# Interface.net
KiCad netlist of a schematic drawn in Altium Designer
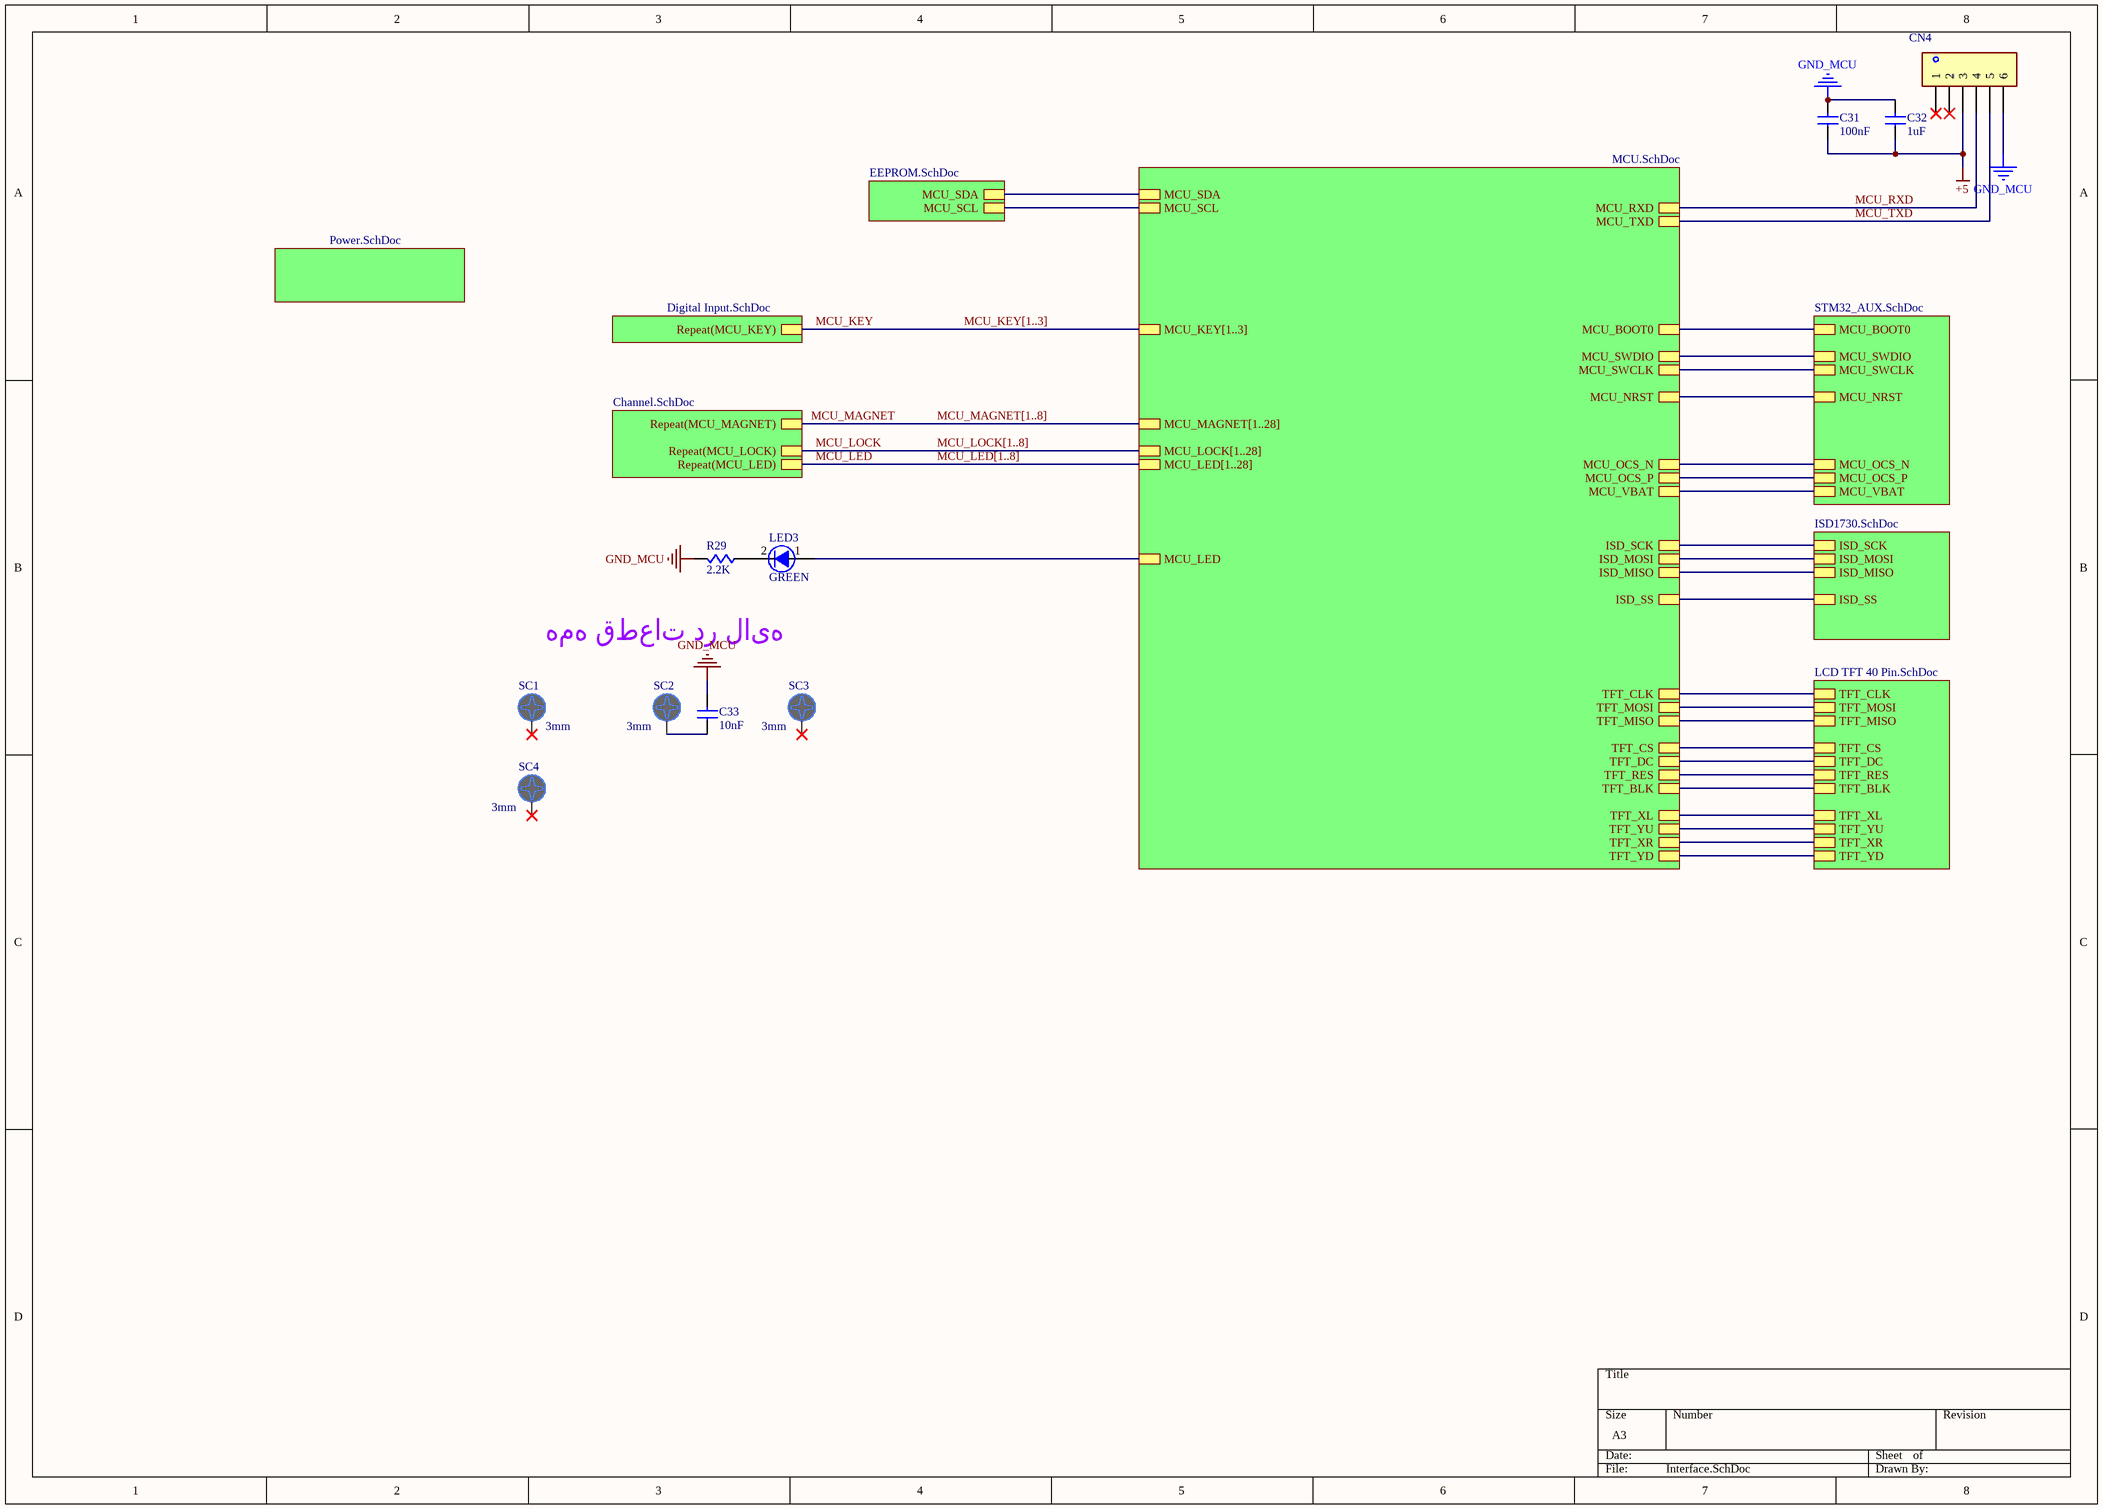
[diagram p0: Interface.SchDoc]

(export (version "E")
  (design (tool "Eeschema 10.0.6"))
  (components
    (comp (ref "C31")
      (value "100nF")
      (footprint "C-0805")
      (description "CAPACITOR")
      (fields
        (field (name "VOLTAGE") "50V")
        (field (name "TOLERANCE") "X7R")
        (field (name "PUBLISHER") "Mahdi Bagherzadeh")
      )
      (libsource (lib "Mahdi-Bagherzadeh") (part "CAP-CER"))
    )
    (comp (ref "C32")
      (value "1uF")
      (footprint "C-0805")
      (description "CAPACITOR")
      (fields
        (field (name "VOLTAGE") "50V")
        (field (name "TOLERANCE") "X7R")
        (field (name "PUBLISHER") "Mahdi Bagherzadeh")
      )
      (libsource (lib "Mahdi-Bagherzadeh") (part "CAP-CER"))
    )
    (comp (ref "C33")
      (value "10nF")
      (footprint "CAP-CER-7x2.5-Ls5")
      (description "CAPACITOR")
      (fields
        (field (name "VOLTAGE") "1KV")
        (field (name "TOLERANCE") "X7R")
        (field (name "PUBLISHER") "Mahdi Bagherzadeh")
      )
      (libsource (lib "Mahdi-Bagherzadeh") (part "CAP-CER"))
    )
    (comp (ref "CN4")
      (value "Connector XH-Straight-THD-2.54mm")
      (footprint "XH-6")
      (description "CONNECTOR")
      (fields (field (name "PUBLISHER") "Mahdi Bagherzadeh"))
      (libsource (lib "Mahdi-Bagherzadeh") (part "CN-6pin"))
    )
    (comp (ref "LED3")
      (value "LED GREEN-1206-SMD")
      (footprint "LED-1206-Y")
      (description "LED")
      (fields (field (name "COLOR") "GREEN") (field (name "PUBLISHER") "Mahdi Bagherzadeh"))
      (libsource (lib "Mahdi-Bagherzadeh") (part "LED"))
    )
    (comp (ref "R29")
      (value "2.2K")
      (footprint "R-0805")
      (description "RESISTOR")
      (fields
        (field (name "TOLERANCE") "5%")
        (field (name "POWER") "1/8W")
        (field (name "PUBLISHER") "Mahdi Bagherzadeh")
      )
      (libsource (lib "Mahdi-Bagherzadeh") (part "RES"))
    )
    (comp (ref "SC1")
      (value "Screw 3mm")
      (footprint "Screw_M3")
      (description "SCREW")
      (fields (field (name "SIZE") "3mm") (field (name "PUBLISHER") "Mahdi Bagherzadeh"))
      (libsource (lib "Mahdi-Bagherzadeh") (part "SCREW"))
    )
    (comp (ref "SC2")
      (value "Screw 3mm")
      (footprint "Screw_M3")
      (description "SCREW")
      (fields (field (name "SIZE") "3mm") (field (name "PUBLISHER") "Mahdi Bagherzadeh"))
      (libsource (lib "Mahdi-Bagherzadeh") (part "SCREW"))
    )
    (comp (ref "SC3")
      (value "Screw 3mm")
      (footprint "Screw_M3")
      (description "SCREW")
      (fields (field (name "SIZE") "3mm") (field (name "PUBLISHER") "Mahdi Bagherzadeh"))
      (libsource (lib "Mahdi-Bagherzadeh") (part "SCREW"))
    )
    (comp (ref "SC4")
      (value "Screw 3mm")
      (footprint "Screw_M3")
      (description "SCREW")
      (fields (field (name "SIZE") "3mm") (field (name "PUBLISHER") "Mahdi Bagherzadeh"))
      (libsource (lib "Mahdi-Bagherzadeh") (part "SCREW"))
    )
  )
  (nets
    (net (code "25") (name "+5") (class "Default")
      (node (ref "C31") (pin "1") (pinfunction "1_1") (pintype "passive"))
      (node (ref "C32") (pin "1") (pinfunction "1_1") (pintype "passive"))
      (node (ref "CN4") (pin "3") (pinfunction "3_3") (pintype "passive"))
    )
    (net (code "34") (name "/MCU_LED_1") (class "Default")
      (node (ref "LED3") (pin "1") (pinfunction "A_1") (pintype "passive"))
    )
    (net (code "42") (name "/MCU_RXD") (class "Default")
      (node (ref "CN4") (pin "4") (pinfunction "4_4") (pintype "passive"))
    )
    (net (code "47") (name "/MCU_TXD") (class "Default")
      (node (ref "CN4") (pin "5") (pinfunction "5_5") (pintype "passive"))
    )
    (net (code "60") (name "GND_MCU") (class "Default")
      (node (ref "C31") (pin "2") (pinfunction "2_2") (pintype "passive"))
      (node (ref "C32") (pin "2") (pinfunction "2_2") (pintype "passive"))
      (node (ref "C33") (pin "2") (pinfunction "2_2") (pintype "passive"))
      (node (ref "CN4") (pin "6") (pinfunction "6_6") (pintype "passive"))
      (node (ref "R29") (pin "2") (pinfunction "2_2") (pintype "passive"))
    )
    (net (code "61") (name "Net-(C33-Pad1)") (class "Default")
      (node (ref "C33") (pin "1") (pinfunction "1_1") (pintype "passive"))
      (node (ref "SC2") (pin "1") (pinfunction "1_1") (pintype "passive"))
    )
    (net (code "62") (name "Net-(LED3-C)") (class "Default")
      (node (ref "LED3") (pin "2") (pinfunction "C_2") (pintype "passive"))
      (node (ref "R29") (pin "1") (pinfunction "1_1") (pintype "passive"))
    )
    (net (code "63") (name "unconnected-(CN4-Pad1)") (class "Default")
      (node (ref "CN4") (pin "1") (pinfunction "1_1") (pintype "passive+no_connect"))
    )
    (net (code "64") (name "unconnected-(CN4-Pad2)") (class "Default")
      (node (ref "CN4") (pin "2") (pinfunction "2_2") (pintype "passive+no_connect"))
    )
    (net (code "65") (name "unconnected-(SC1-Pad1)") (class "Default")
      (node (ref "SC1") (pin "1") (pinfunction "1_1") (pintype "passive+no_connect"))
    )
    (net (code "66") (name "unconnected-(SC3-Pad1)") (class "Default")
      (node (ref "SC3") (pin "1") (pinfunction "1_1") (pintype "passive+no_connect"))
    )
    (net (code "67") (name "unconnected-(SC4-Pad1)") (class "Default")
      (node (ref "SC4") (pin "1") (pinfunction "1_1") (pintype "passive+no_connect"))
    )
  )
)
